# OpenBookReader.net
KiCad netlist of a schematic drawn in EAGLE
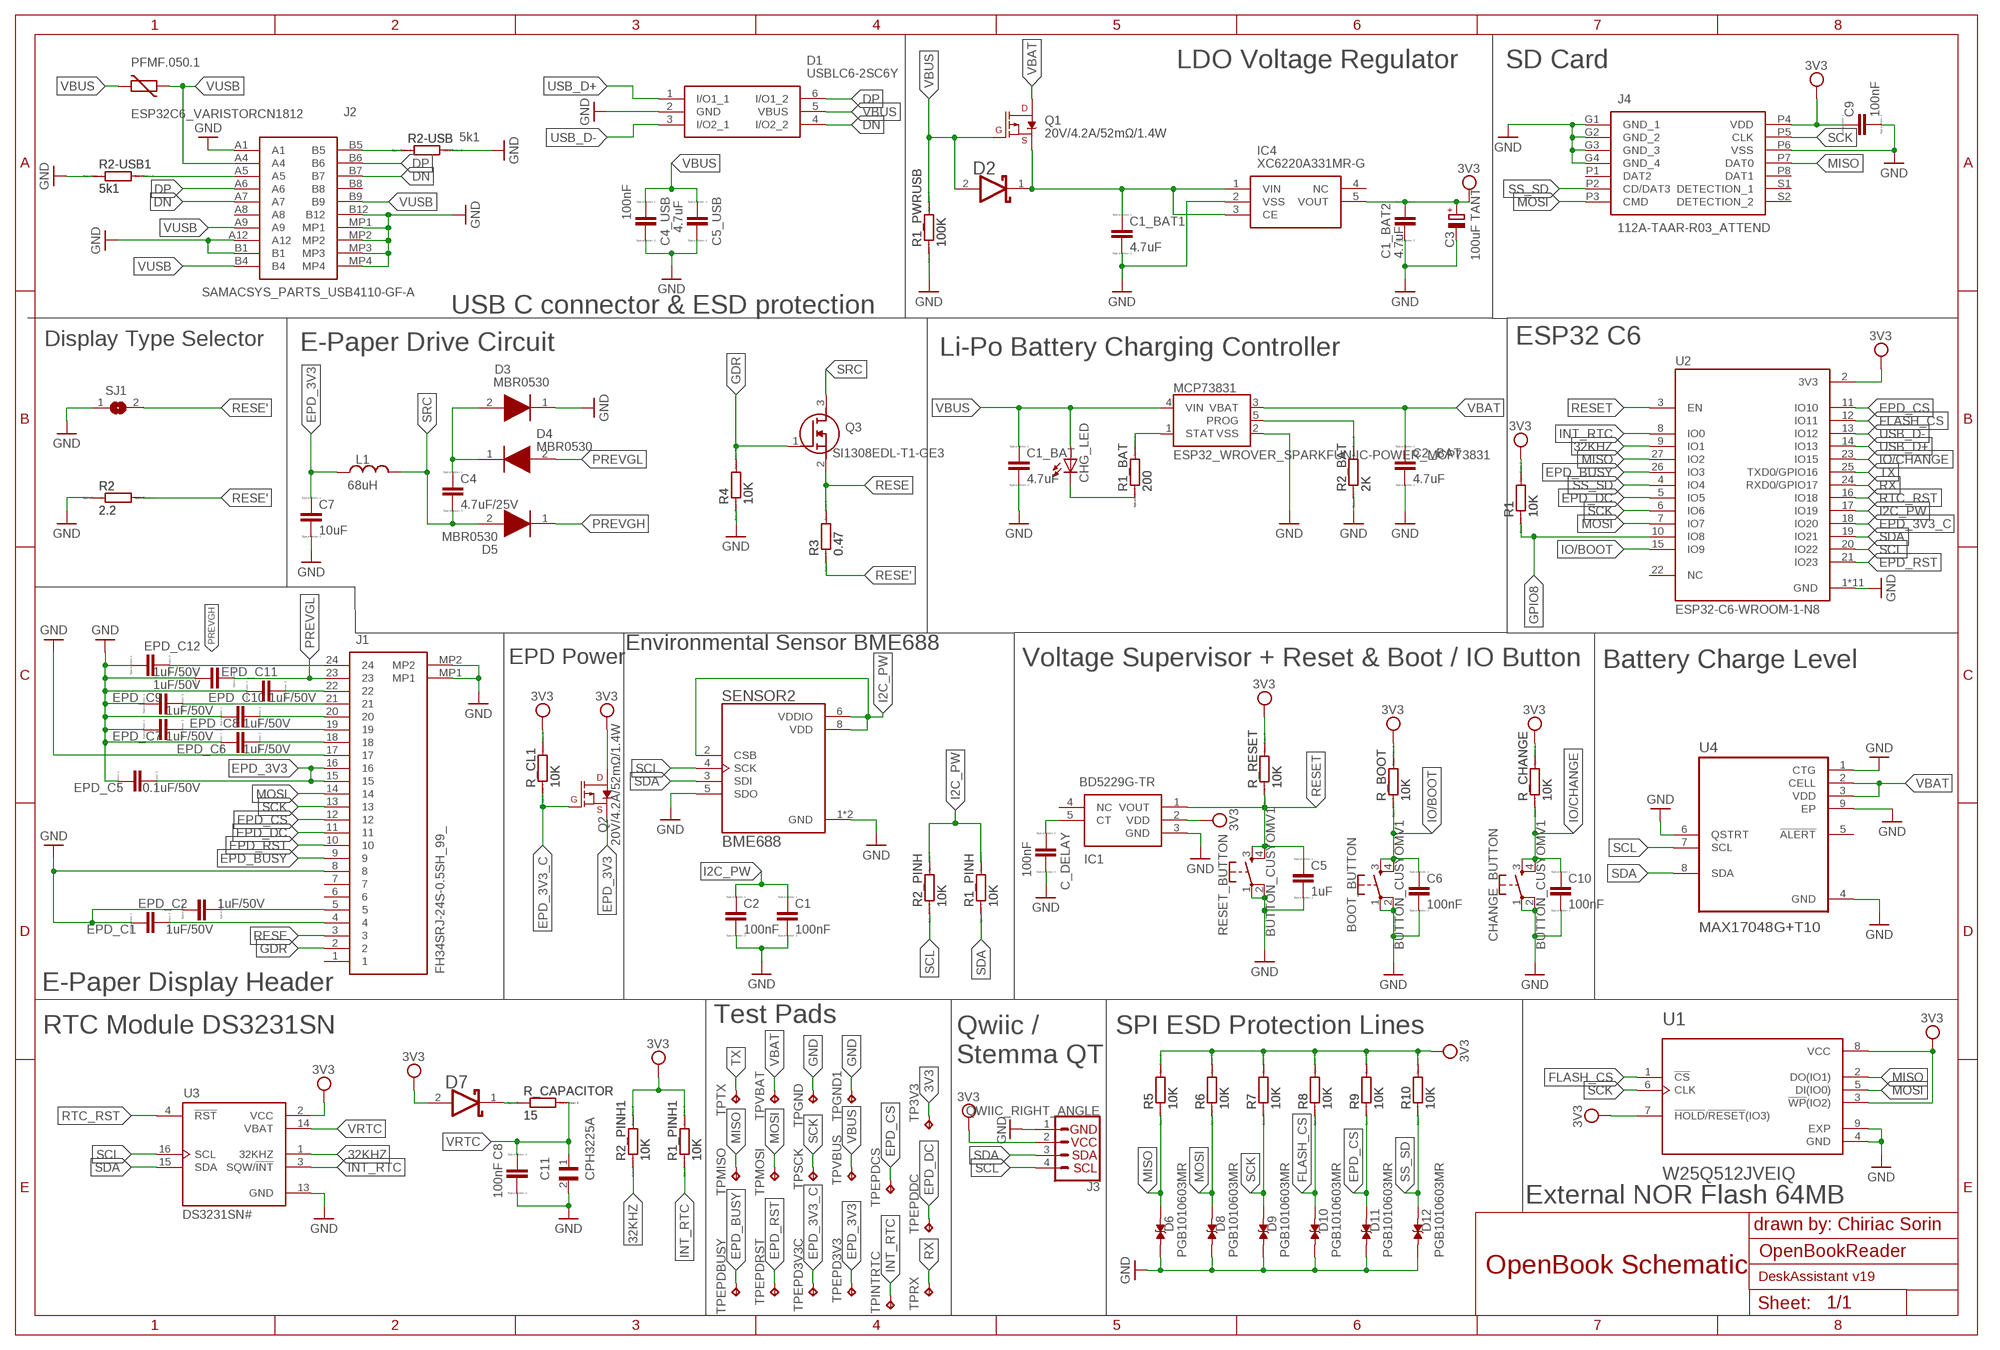
[diagram p0: schematic, sheet 1]

(export (version "E")
  (design (tool "Eeschema 10.0.6"))
  (components
    (comp (ref "BOOT_BUTTON")
      (value "BUTTON_CUSYOMV1")
      (footprint "eagle-import:MYBUTTON")
      (libsource (lib "eagle-import") (part "BUTTON_CUSYOMV1"))
    )
    (comp (ref "C1")
      (value "100nF")
      (footprint "eagle-import:EAGLE-LTSPICE_C0402")
      (libsource (lib "eagle-import") (part "EAGLE-LTSPICE_CC0402"))
    )
    (comp (ref "C1_BAT")
      (value "4.7uF")
      (footprint "eagle-import:EAGLE-LTSPICE_C0402")
      (libsource (lib "eagle-import") (part "EAGLE-LTSPICE_CC0402"))
    )
    (comp (ref "C1_BAT1")
      (value "4.7uF")
      (footprint "eagle-import:EAGLE-LTSPICE_C0402")
      (libsource (lib "eagle-import") (part "EAGLE-LTSPICE_CC0402"))
    )
    (comp (ref "C1_BAT2")
      (value "4.7uF")
      (footprint "eagle-import:EAGLE-LTSPICE_C0402")
      (libsource (lib "eagle-import") (part "EAGLE-LTSPICE_CC0402"))
    )
    (comp (ref "C2")
      (value "100nF")
      (footprint "eagle-import:EAGLE-LTSPICE_C0402")
      (libsource (lib "eagle-import") (part "EAGLE-LTSPICE_CC0402"))
    )
    (comp (ref "C2_BAT")
      (value "4.7uF")
      (footprint "eagle-import:EAGLE-LTSPICE_C0402")
      (libsource (lib "eagle-import") (part "EAGLE-LTSPICE_CC0402"))
    )
    (comp (ref "C3")
      (value "100uF TANT")
      (footprint "eagle-import:RCL_CT3528")
      (libsource (lib "eagle-import") (part "RCL_CPOL-EUCT3528"))
    )
    (comp (ref "C4")
      (value "4.7uF/25V")
      (footprint "eagle-import:EAGLE-LTSPICE_C0402")
      (libsource (lib "eagle-import") (part "EAGLE-LTSPICE_CC0402"))
    )
    (comp (ref "C4_USB")
      (value "100nF")
      (footprint "eagle-import:EAGLE-LTSPICE_C0402")
      (libsource (lib "eagle-import") (part "EAGLE-LTSPICE_CC0402"))
    )
    (comp (ref "C5")
      (value "1uF")
      (footprint "eagle-import:EAGLE-LTSPICE_C0402")
      (libsource (lib "eagle-import") (part "EAGLE-LTSPICE_CC0402"))
    )
    (comp (ref "C5_USB")
      (value "4.7uF")
      (footprint "eagle-import:EAGLE-LTSPICE_C0402")
      (libsource (lib "eagle-import") (part "EAGLE-LTSPICE_CC0402"))
    )
    (comp (ref "C6")
      (value "100nF")
      (footprint "eagle-import:EAGLE-LTSPICE_C0402")
      (libsource (lib "eagle-import") (part "EAGLE-LTSPICE_CC0402"))
    )
    (comp (ref "C7")
      (value "10uF")
      (footprint "eagle-import:EAGLE-LTSPICE_C0402")
      (libsource (lib "eagle-import") (part "EAGLE-LTSPICE_CC0402"))
    )
    (comp (ref "C8")
      (value "100nF")
      (footprint "eagle-import:EAGLE-LTSPICE_C0402")
      (libsource (lib "eagle-import") (part "EAGLE-LTSPICE_CC0402"))
    )
    (comp (ref "C9")
      (value "100nF")
      (footprint "eagle-import:EAGLE-LTSPICE_C0402")
      (libsource (lib "eagle-import") (part "EAGLE-LTSPICE_CC0402"))
    )
    (comp (ref "C10")
      (value "100nF")
      (footprint "eagle-import:EAGLE-LTSPICE_C0402")
      (libsource (lib "eagle-import") (part "EAGLE-LTSPICE_CC0402"))
    )
    (comp (ref "C11")
      (value "CPH3225A")
      (footprint "eagle-import:CAPCP3225X100N")
      (fields (field (name "MF") "Seiko Instruments"))
      (libsource (lib "eagle-import") (part "CPH3225A"))
    )
    (comp (ref "CHANGE_BUTTON")
      (value "BUTTON_CUSYOMV1")
      (footprint "eagle-import:MYBUTTON")
      (libsource (lib "eagle-import") (part "BUTTON_CUSYOMV1"))
    )
    (comp (ref "CHG_LED")
      (value "ADAFRUIT_LEDCHIP-LED0603")
      (footprint "eagle-import:ADAFRUIT_CHIP-LED0603")
      (libsource (lib "eagle-import") (part "ADAFRUIT_LEDCHIP-LED0603"))
    )
    (comp (ref "C_DELAY")
      (value "100nF")
      (footprint "eagle-import:EAGLE-LTSPICE_C0402")
      (libsource (lib "eagle-import") (part "EAGLE-LTSPICE_CC0402"))
    )
    (comp (ref "D1")
      (value "USBLC6-2SC6Y")
      (footprint "eagle-import:SOT95P280X145-6N")
      (fields (field (name "MF") "STMicroelectronics"))
      (libsource (lib "eagle-import") (part "USBLC6-2SC6Y"))
    )
    (comp (ref "D2")
      (value "ESP32_WROVER_AVX---SD0805S020S1R0_AVX_SD0805S020S1R0_0_0AVX_SD0805S020S1R0_0_0")
      (footprint "eagle-import:ESP32_WROVER_AVX---SD0805S020S1R0_AVX_SD0805S020S1R0_0")
      (fields
        (field (name "DIGIKEY_PART_NUMBER") "478-7800-1-ND")
        (field (name "MF") "AVX")
        (field (name "MOUSER_PART_NUMBER") "581-SD0805S020S1R0")
      )
      (libsource (lib "eagle-import") (part "ESP32_WROVER_AVX---SD0805S020S1R0_AVX_SD0805S020S1R0_0_0AVX_SD0805S020S1R0_0_0"))
    )
    (comp (ref "D3")
      (value "MBR0530")
      (footprint "eagle-import:SOD3716X135N")
      (fields (field (name "MF") "ON Semiconductor"))
      (libsource (lib "eagle-import") (part "MBR0530"))
    )
    (comp (ref "D4")
      (value "MBR0530")
      (footprint "eagle-import:SOD3716X135N")
      (fields (field (name "MF") "ON Semiconductor"))
      (libsource (lib "eagle-import") (part "MBR0530"))
    )
    (comp (ref "D5")
      (value "MBR0530")
      (footprint "eagle-import:SOD3716X135N")
      (fields (field (name "MF") "ON Semiconductor"))
      (libsource (lib "eagle-import") (part "MBR0530"))
    )
    (comp (ref "D6")
      (value "PGB1010603MR")
      (footprint "eagle-import:DIOC1608X36N")
      (fields (field (name "MF") "Littelfuse Inc."))
      (libsource (lib "eagle-import") (part "PGB1010603MR"))
    )
    (comp (ref "D7")
      (value "ESP32_WROVER_AVX---SD0805S020S1R0_AVX_SD0805S020S1R0_0_0AVX_SD0805S020S1R0_0_0")
      (footprint "eagle-import:ESP32_WROVER_AVX---SD0805S020S1R0_AVX_SD0805S020S1R0_0")
      (fields
        (field (name "DIGIKEY_PART_NUMBER") "478-7800-1-ND")
        (field (name "MF") "AVX")
        (field (name "MOUSER_PART_NUMBER") "581-SD0805S020S1R0")
      )
      (libsource (lib "eagle-import") (part "ESP32_WROVER_AVX---SD0805S020S1R0_AVX_SD0805S020S1R0_0_0AVX_SD0805S020S1R0_0_0"))
    )
    (comp (ref "D8")
      (value "PGB1010603MR")
      (footprint "eagle-import:DIOC1608X36N")
      (fields (field (name "MF") "Littelfuse Inc."))
      (libsource (lib "eagle-import") (part "PGB1010603MR"))
    )
    (comp (ref "D9")
      (value "PGB1010603MR")
      (footprint "eagle-import:DIOC1608X36N")
      (fields (field (name "MF") "Littelfuse Inc."))
      (libsource (lib "eagle-import") (part "PGB1010603MR"))
    )
    (comp (ref "D10")
      (value "PGB1010603MR")
      (footprint "eagle-import:DIOC1608X36N")
      (fields (field (name "MF") "Littelfuse Inc."))
      (libsource (lib "eagle-import") (part "PGB1010603MR"))
    )
    (comp (ref "D11")
      (value "PGB1010603MR")
      (footprint "eagle-import:DIOC1608X36N")
      (fields (field (name "MF") "Littelfuse Inc."))
      (libsource (lib "eagle-import") (part "PGB1010603MR"))
    )
    (comp (ref "D12")
      (value "PGB1010603MR")
      (footprint "eagle-import:DIOC1608X36N")
      (fields (field (name "MF") "Littelfuse Inc."))
      (libsource (lib "eagle-import") (part "PGB1010603MR"))
    )
    (comp (ref "EPD_C1")
      (value "1uF/50V")
      (footprint "eagle-import:EAGLE-LTSPICE_C0402")
      (libsource (lib "eagle-import") (part "EAGLE-LTSPICE_CC0402"))
    )
    (comp (ref "EPD_C2")
      (value "1uF/50V")
      (footprint "eagle-import:EAGLE-LTSPICE_C0402")
      (libsource (lib "eagle-import") (part "EAGLE-LTSPICE_CC0402"))
    )
    (comp (ref "EPD_C5")
      (value "0.1uF/50V")
      (footprint "eagle-import:EAGLE-LTSPICE_C0402")
      (libsource (lib "eagle-import") (part "EAGLE-LTSPICE_CC0402"))
    )
    (comp (ref "EPD_C6")
      (value "1uF/50V")
      (footprint "eagle-import:EAGLE-LTSPICE_C0402")
      (libsource (lib "eagle-import") (part "EAGLE-LTSPICE_CC0402"))
    )
    (comp (ref "EPD_C7")
      (value "1uF/50V")
      (footprint "eagle-import:EAGLE-LTSPICE_C0402")
      (libsource (lib "eagle-import") (part "EAGLE-LTSPICE_CC0402"))
    )
    (comp (ref "EPD_C8")
      (value "1uF/50V")
      (footprint "eagle-import:EAGLE-LTSPICE_C0402")
      (libsource (lib "eagle-import") (part "EAGLE-LTSPICE_CC0402"))
    )
    (comp (ref "EPD_C9")
      (value "1uF/50V")
      (footprint "eagle-import:EAGLE-LTSPICE_C0402")
      (libsource (lib "eagle-import") (part "EAGLE-LTSPICE_CC0402"))
    )
    (comp (ref "EPD_C10")
      (value "1uF/50V")
      (footprint "eagle-import:EAGLE-LTSPICE_C0402")
      (libsource (lib "eagle-import") (part "EAGLE-LTSPICE_CC0402"))
    )
    (comp (ref "EPD_C11")
      (value "1uF/50V")
      (footprint "eagle-import:EAGLE-LTSPICE_C0402")
      (libsource (lib "eagle-import") (part "EAGLE-LTSPICE_CC0402"))
    )
    (comp (ref "EPD_C12")
      (value "1uF/50V")
      (footprint "eagle-import:EAGLE-LTSPICE_C0402")
      (libsource (lib "eagle-import") (part "EAGLE-LTSPICE_CC0402"))
    )
    (comp (ref "IC1")
      (value "BD5229G-TR")
      (footprint "eagle-import:SOT95P280X125-5N")
      (fields (field (name "MOUSER_PART_NUMBER") "755-BD5229G-TR"))
      (libsource (lib "eagle-import") (part "BD5229G-TR"))
    )
    (comp (ref "IC4")
      (value "XC6220A331MR-G")
      (footprint "eagle-import:SOT95P280X120-5N")
      (fields (field (name "MOUSER_PART_NUMBER") "865-XC6220A331MR-G"))
      (libsource (lib "eagle-import") (part "XC6220A331MR-G"))
    )
    (comp (ref "J1")
      (value "FH34SRJ-24S-0.5SH_99_")
      (footprint "eagle-import:FH34SRJ24S05SH99")
      (fields
        (field (name "MANUFACTURER_PART_NUMBER") "FH34SRJ-24S-0.5SH(99)")
        (field (name "MOUSER_PART_NUMBER") "798-FH34SRJ24S05SH99")
      )
      (libsource (lib "eagle-import") (part "FH34SRJ-24S-0.5SH_99_"))
    )
    (comp (ref "J2")
      (value "SAMACSYS_PARTS_USB4110-GF-A")
      (footprint "eagle-import:SAMACSYS_PARTS_USB4110GFA")
      (fields
        (field (name "MANUFACTURER_PART_NUMBER") "USB4110-GF-A")
        (field (name "MOUSER_PART_NUMBER") "640-USB4110-GF-A")
      )
      (libsource (lib "eagle-import") (part "SAMACSYS_PARTS_USB4110-GF-A"))
    )
    (comp (ref "J3")
      (value "QWIIC_RIGHT_ANGLE")
      (footprint "eagle-import:JST04_1MM_RA")
      (libsource (lib "eagle-import") (part "QWIIC_CONNECTORJS-1MM"))
    )
    (comp (ref "J4")
      (value "112A-TAAR-R03_ATTEND")
      (footprint "eagle-import:112ATAARR03ATTEND")
      (fields (field (name "MANUFACTURER_PART_NUMBER") "112A-TAAR-R03 ATTEND"))
      (libsource (lib "eagle-import") (part "112A-TAAR-R03_ATTEND"))
    )
    (comp (ref "L1")
      (value "68uH")
      (footprint "eagle-import:INDC1006X60N")
      (libsource (lib "eagle-import") (part "INDUCTORCHIP-0402(1006-METRIC)_"))
    )
    (comp (ref "MCP73831")
      (value "ESP32_WROVER_SPARKFUN-IC-POWER_MCP73831")
      (footprint "eagle-import:ESP32_WROVER_SPARKFUN-IC-POWER_SOT23-5")
      (libsource (lib "eagle-import") (part "ESP32_WROVER_SPARKFUN-IC-POWER_MCP73831"))
    )
    (comp (ref "PFMF.050.1")
      (value "ESP32C6_VARISTORCN1812")
      (footprint "eagle-import:ESP32C6_VARISTOR_CT_CN1812")
      (libsource (lib "eagle-import") (part "ESP32C6_VARISTORCN1812"))
    )
    (comp (ref "Q1")
      (value "20V/4.2A/52mΩ/1.4W")
      (footprint "eagle-import:ESP32_WROVER_SPARKFUN-DISCRETESEMI_SOT23-3")
      (libsource (lib "eagle-import") (part "ESP32_WROVER_SPARKFUN-DISCRETESEMI_MOSFET_PCH-DMG2305UX-7"))
    )
    (comp (ref "Q2")
      (value "20V/4.2A/52mΩ/1.4W")
      (footprint "eagle-import:ESP32_WROVER_SPARKFUN-DISCRETESEMI_SOT23-3")
      (libsource (lib "eagle-import") (part "ESP32_WROVER_SPARKFUN-DISCRETESEMI_MOSFET_PCH-DMG2305UX-7"))
    )
    (comp (ref "Q3")
      (value "SI1308EDL-T1-GE3")
      (footprint "eagle-import:SOT65P210X110-3N")
      (fields (field (name "MF") "Vishay Siliconix"))
      (libsource (lib "eagle-import") (part "SI1308EDL-T1-GE3"))
    )
    (comp (ref "R1")
      (value "10K")
      (footprint "eagle-import:ESP32_WROVER_EAGLE-LTSPICE_R0402")
      (libsource (lib "eagle-import") (part "ESP32_WROVER_EAGLE-LTSPICE_RR0402"))
    )
    (comp (ref "R1_BAT")
      (value "200")
      (footprint "eagle-import:ESP32_WROVER_EAGLE-LTSPICE_R0402")
      (libsource (lib "eagle-import") (part "ESP32_WROVER_EAGLE-LTSPICE_RR0402"))
    )
    (comp (ref "R1_PINH")
      (value "10K")
      (footprint "eagle-import:ESP32_WROVER_EAGLE-LTSPICE_R0402")
      (libsource (lib "eagle-import") (part "ESP32_WROVER_EAGLE-LTSPICE_RR0402"))
    )
    (comp (ref "R1_PINH1")
      (value "10K")
      (footprint "eagle-import:ESP32_WROVER_EAGLE-LTSPICE_R0402")
      (libsource (lib "eagle-import") (part "ESP32_WROVER_EAGLE-LTSPICE_RR0402"))
    )
    (comp (ref "R1_PWRUSB")
      (value "100K")
      (footprint "eagle-import:ESP32_WROVER_EAGLE-LTSPICE_R0402")
      (libsource (lib "eagle-import") (part "ESP32_WROVER_EAGLE-LTSPICE_RR0402"))
    )
    (comp (ref "R2")
      (value "2.2")
      (footprint "eagle-import:ESP32_WROVER_EAGLE-LTSPICE_R0402")
      (libsource (lib "eagle-import") (part "ESP32_WROVER_EAGLE-LTSPICE_RR0402"))
    )
    (comp (ref "R2-USB")
      (value "5k1")
      (footprint "eagle-import:ESP32_WROVER_EAGLE-LTSPICE_R0402")
      (libsource (lib "eagle-import") (part "ESP32_WROVER_EAGLE-LTSPICE_RR0402"))
    )
    (comp (ref "R2-USB1")
      (value "5k1")
      (footprint "eagle-import:ESP32_WROVER_EAGLE-LTSPICE_R0402")
      (libsource (lib "eagle-import") (part "ESP32_WROVER_EAGLE-LTSPICE_RR0402"))
    )
    (comp (ref "R2_BAT")
      (value "2K")
      (footprint "eagle-import:ESP32_WROVER_EAGLE-LTSPICE_R0402")
      (libsource (lib "eagle-import") (part "ESP32_WROVER_EAGLE-LTSPICE_RR0402"))
    )
    (comp (ref "R2_PINH")
      (value "10K")
      (footprint "eagle-import:ESP32_WROVER_EAGLE-LTSPICE_R0402")
      (libsource (lib "eagle-import") (part "ESP32_WROVER_EAGLE-LTSPICE_RR0402"))
    )
    (comp (ref "R2_PINH1")
      (value "10K")
      (footprint "eagle-import:ESP32_WROVER_EAGLE-LTSPICE_R0402")
      (libsource (lib "eagle-import") (part "ESP32_WROVER_EAGLE-LTSPICE_RR0402"))
    )
    (comp (ref "R3")
      (value "0.47")
      (footprint "eagle-import:ESP32_WROVER_EAGLE-LTSPICE_R0402")
      (libsource (lib "eagle-import") (part "ESP32_WROVER_EAGLE-LTSPICE_RR0402"))
    )
    (comp (ref "R4")
      (value "10K")
      (footprint "eagle-import:ESP32_WROVER_EAGLE-LTSPICE_R0402")
      (libsource (lib "eagle-import") (part "ESP32_WROVER_EAGLE-LTSPICE_RR0402"))
    )
    (comp (ref "R5")
      (value "10K")
      (footprint "eagle-import:ESP32_WROVER_EAGLE-LTSPICE_R0402")
      (libsource (lib "eagle-import") (part "ESP32_WROVER_EAGLE-LTSPICE_RR0402"))
    )
    (comp (ref "R6")
      (value "10K")
      (footprint "eagle-import:ESP32_WROVER_EAGLE-LTSPICE_R0402")
      (libsource (lib "eagle-import") (part "ESP32_WROVER_EAGLE-LTSPICE_RR0402"))
    )
    (comp (ref "R7")
      (value "10K")
      (footprint "eagle-import:ESP32_WROVER_EAGLE-LTSPICE_R0402")
      (libsource (lib "eagle-import") (part "ESP32_WROVER_EAGLE-LTSPICE_RR0402"))
    )
    (comp (ref "R8")
      (value "10K")
      (footprint "eagle-import:ESP32_WROVER_EAGLE-LTSPICE_R0402")
      (libsource (lib "eagle-import") (part "ESP32_WROVER_EAGLE-LTSPICE_RR0402"))
    )
    (comp (ref "R9")
      (value "10K")
      (footprint "eagle-import:ESP32_WROVER_EAGLE-LTSPICE_R0402")
      (libsource (lib "eagle-import") (part "ESP32_WROVER_EAGLE-LTSPICE_RR0402"))
    )
    (comp (ref "R10")
      (value "10K")
      (footprint "eagle-import:ESP32_WROVER_EAGLE-LTSPICE_R0402")
      (libsource (lib "eagle-import") (part "ESP32_WROVER_EAGLE-LTSPICE_RR0402"))
    )
    (comp (ref "RESET_BUTTON")
      (value "BUTTON_CUSYOMV1")
      (footprint "eagle-import:MYBUTTON")
      (libsource (lib "eagle-import") (part "BUTTON_CUSYOMV1"))
    )
    (comp (ref "R_BOOT")
      (value "10K")
      (footprint "eagle-import:ESP32_WROVER_EAGLE-LTSPICE_R0402")
      (libsource (lib "eagle-import") (part "ESP32_WROVER_EAGLE-LTSPICE_RR0402"))
    )
    (comp (ref "R_CAPACITOR")
      (value "15")
      (footprint "eagle-import:ESP32_WROVER_EAGLE-LTSPICE_R0402")
      (libsource (lib "eagle-import") (part "ESP32_WROVER_EAGLE-LTSPICE_RR0402"))
    )
    (comp (ref "R_CHANGE")
      (value "10K")
      (footprint "eagle-import:ESP32_WROVER_EAGLE-LTSPICE_R0402")
      (libsource (lib "eagle-import") (part "ESP32_WROVER_EAGLE-LTSPICE_RR0402"))
    )
    (comp (ref "R_CL1")
      (value "10K")
      (footprint "eagle-import:ESP32_WROVER_EAGLE-LTSPICE_R0402")
      (libsource (lib "eagle-import") (part "ESP32_WROVER_EAGLE-LTSPICE_RR0402"))
    )
    (comp (ref "R_RESET")
      (value "10K")
      (footprint "eagle-import:ESP32_WROVER_EAGLE-LTSPICE_R0402")
      (libsource (lib "eagle-import") (part "ESP32_WROVER_EAGLE-LTSPICE_RR0402"))
    )
    (comp (ref "SENSOR2")
      (value "BME688")
      (footprint "eagle-import:ESP32_WROVER_BME680_PSON80P300X300X100-8N")
      (fields (field (name "MF") "Bosch Sensortec") (field (name "MP") "BME680"))
      (libsource (lib "eagle-import") (part "ESP32_WROVER_BME680_BME680"))
    )
    (comp (ref "SJ1") (value "SJ") (footprint "eagle-import:SJ") (libsource (lib "eagle-import") (part "SJ")))
    (comp (ref "TP3V3")
      (value "TPTP20R")
      (footprint "eagle-import:TP20R")
      (libsource (lib "eagle-import") (part "TPTP20R"))
    )
    (comp (ref "TPEPD3V3")
      (value "TPTP20R")
      (footprint "eagle-import:TP20R")
      (libsource (lib "eagle-import") (part "TPTP20R"))
    )
    (comp (ref "TPEPD3V3C")
      (value "TPTP20R")
      (footprint "eagle-import:TP20R")
      (libsource (lib "eagle-import") (part "TPTP20R"))
    )
    (comp (ref "TPEPDBUSY")
      (value "TPTP20R")
      (footprint "eagle-import:TP20R")
      (libsource (lib "eagle-import") (part "TPTP20R"))
    )
    (comp (ref "TPEPDCS")
      (value "TPTP20R")
      (footprint "eagle-import:TP20R")
      (libsource (lib "eagle-import") (part "TPTP20R"))
    )
    (comp (ref "TPEPDDC")
      (value "TPTP20R")
      (footprint "eagle-import:TP20R")
      (libsource (lib "eagle-import") (part "TPTP20R"))
    )
    (comp (ref "TPEPDRST")
      (value "TPTP20R")
      (footprint "eagle-import:TP20R")
      (libsource (lib "eagle-import") (part "TPTP20R"))
    )
    (comp (ref "TPGND")
      (value "TPTP20R")
      (footprint "eagle-import:TP20R")
      (libsource (lib "eagle-import") (part "TPTP20R"))
    )
    (comp (ref "TPGND1")
      (value "TPTP20R")
      (footprint "eagle-import:TP20R")
      (libsource (lib "eagle-import") (part "TPTP20R"))
    )
    (comp (ref "TPINTRTC")
      (value "TPTP20R")
      (footprint "eagle-import:TP20R")
      (libsource (lib "eagle-import") (part "TPTP20R"))
    )
    (comp (ref "TPMISO")
      (value "TPTP20R")
      (footprint "eagle-import:TP20R")
      (libsource (lib "eagle-import") (part "TPTP20R"))
    )
    (comp (ref "TPMOSI")
      (value "TPTP20R")
      (footprint "eagle-import:TP20R")
      (libsource (lib "eagle-import") (part "TPTP20R"))
    )
    (comp (ref "TPRX")
      (value "TPTP20R")
      (footprint "eagle-import:TP20R")
      (libsource (lib "eagle-import") (part "TPTP20R"))
    )
    (comp (ref "TPSCK")
      (value "TPTP20R")
      (footprint "eagle-import:TP20R")
      (libsource (lib "eagle-import") (part "TPTP20R"))
    )
    (comp (ref "TPTX")
      (value "TPTP20R")
      (footprint "eagle-import:TP20R")
      (libsource (lib "eagle-import") (part "TPTP20R"))
    )
    (comp (ref "TPVBAT")
      (value "TPTP20R")
      (footprint "eagle-import:TP20R")
      (libsource (lib "eagle-import") (part "TPTP20R"))
    )
    (comp (ref "TPVBUS")
      (value "TPTP20R")
      (footprint "eagle-import:TP20R")
      (libsource (lib "eagle-import") (part "TPTP20R"))
    )
    (comp (ref "U1")
      (value "W25Q512JVEIQ")
      (footprint "eagle-import:SON127P600X800X80-9N")
      (fields (field (name "MF") "Winbond Electronics"))
      (libsource (lib "eagle-import") (part "W25Q512JVEIQ"))
    )
    (comp (ref "U2")
      (value "ESP32-C6-WROOM-1-N8")
      (footprint "eagle-import:XCVR_ESP32-C6-WROOM-1-N8")
      (fields (field (name "MF") "Espressif Systems"))
      (libsource (lib "eagle-import") (part "ESP32-C6-WROOM-1-N8"))
    )
    (comp (ref "U3")
      (value "DS3231SN#")
      (footprint "eagle-import:SOIC127P1032X265-16N")
      (fields (field (name "MF") "Analog Devices"))
      (libsource (lib "eagle-import") (part "DS3231SN#"))
    )
    (comp (ref "U4")
      (value "MAX17048G+T10")
      (footprint "eagle-import:SON50P200X200X80-9N")
      (fields (field (name "MF") "Analog Devices"))
      (libsource (lib "eagle-import") (part "MAX17048G+T10"))
    )
  )
  (nets
    (net (code "1") (name "3V3") (class "Default")
      (node (ref "C1_BAT2") (pin "1") (pinfunction "1_1") (pintype "passive"))
      (node (ref "C3") (pin "+") (pinfunction "+_+") (pintype "passive"))
      (node (ref "C9") (pin "1") (pinfunction "1_1") (pintype "passive"))
      (node (ref "D7") (pin "2") (pinfunction "ANODE_2") (pintype "bidirectional"))
      (node (ref "IC1") (pin "2") (pinfunction "VDD_2") (pintype "bidirectional"))
      (node (ref "IC4") (pin "5") (pinfunction "VOUT_5") (pintype "bidirectional"))
      (node (ref "J3") (pin "2") (pinfunction "2_2") (pintype "power_in"))
      (node (ref "J4") (pin "P4") (pinfunction "VDD_P4") (pintype "bidirectional"))
      (node (ref "Q2") (pin "3") (pinfunction "D_3") (pintype "bidirectional"))
      (node (ref "R1") (pin "2") (pinfunction "2_2") (pintype "passive"))
      (node (ref "R10") (pin "2") (pinfunction "2_2") (pintype "passive"))
      (node (ref "R1_PINH1") (pin "2") (pinfunction "2_2") (pintype "passive"))
      (node (ref "R2_PINH1") (pin "2") (pinfunction "2_2") (pintype "passive"))
      (node (ref "R5") (pin "2") (pinfunction "2_2") (pintype "passive"))
      (node (ref "R6") (pin "2") (pinfunction "2_2") (pintype "passive"))
      (node (ref "R7") (pin "2") (pinfunction "2_2") (pintype "passive"))
      (node (ref "R8") (pin "2") (pinfunction "2_2") (pintype "passive"))
      (node (ref "R9") (pin "2") (pinfunction "2_2") (pintype "passive"))
      (node (ref "R_BOOT") (pin "2") (pinfunction "2_2") (pintype "passive"))
      (node (ref "R_CHANGE") (pin "2") (pinfunction "2_2") (pintype "passive"))
      (node (ref "R_CL1") (pin "2") (pinfunction "2_2") (pintype "passive"))
      (node (ref "R_RESET") (pin "2") (pinfunction "2_2") (pintype "passive"))
      (node (ref "TP3V3") (pin "TP") (pinfunction "TP_TP") (pintype "input"))
      (node (ref "U1") (pin "3") (pinfunction "~{WP}(IO2)_3") (pintype "bidirectional"))
      (node (ref "U1") (pin "7") (pinfunction "~{HOLD}/~{RESET}(IO3)_7") (pintype "bidirectional"))
      (node (ref "U1") (pin "8") (pinfunction "VCC_8") (pintype "power_in"))
      (node (ref "U2") (pin "2") (pinfunction "3V3_2") (pintype "power_in"))
      (node (ref "U3") (pin "2") (pinfunction "VCC_2") (pintype "power_in"))
    )
    (net (code "2") (name "32KHZ") (class "Default")
      (node (ref "R2_PINH1") (pin "1") (pinfunction "1_1") (pintype "passive"))
      (node (ref "U2") (pin "9") (pinfunction "IO1_9") (pintype "bidirectional"))
      (node (ref "U3") (pin "1") (pinfunction "32KHZ_1") (pintype "output"))
    )
    (net (code "3") (name "DN") (class "Default")
      (node (ref "D1") (pin "4") (pinfunction "I/O2_2_4") (pintype "bidirectional"))
      (node (ref "J2") (pin "A7") (pinfunction "A7_A7") (pintype "bidirectional"))
      (node (ref "J2") (pin "B7") (pinfunction "B7_B7") (pintype "bidirectional"))
    )
    (net (code "4") (name "DP") (class "Default")
      (node (ref "D1") (pin "6") (pinfunction "I/O1_2_6") (pintype "bidirectional"))
      (node (ref "J2") (pin "A6") (pinfunction "A6_A6") (pintype "bidirectional"))
      (node (ref "J2") (pin "B6") (pinfunction "B6_B6") (pintype "bidirectional"))
    )
    (net (code "5") (name "EPD_3V3") (class "Default")
      (node (ref "C7") (pin "1") (pinfunction "1_1") (pintype "passive"))
      (node (ref "EPD_C5") (pin "2") (pinfunction "2_2") (pintype "passive"))
      (node (ref "J1") (pin "15") (pinfunction "15_15") (pintype "bidirectional"))
      (node (ref "J1") (pin "16") (pinfunction "16_16") (pintype "bidirectional"))
      (node (ref "L1") (pin "1") (pinfunction "1_1") (pintype "passive"))
      (node (ref "Q2") (pin "2") (pinfunction "S_2") (pintype "bidirectional"))
      (node (ref "TPEPD3V3") (pin "TP") (pinfunction "TP_TP") (pintype "input"))
    )
    (net (code "6") (name "EPD_3V3_C") (class "Default")
      (node (ref "Q2") (pin "1") (pinfunction "G_1") (pintype "bidirectional"))
      (node (ref "R_CL1") (pin "1") (pinfunction "1_1") (pintype "passive"))
      (node (ref "TPEPD3V3C") (pin "TP") (pinfunction "TP_TP") (pintype "input"))
      (node (ref "U2") (pin "18") (pinfunction "IO20_18") (pintype "bidirectional"))
    )
    (net (code "7") (name "EPD_BUSY") (class "Default")
      (node (ref "J1") (pin "9") (pinfunction "9_9") (pintype "bidirectional"))
      (node (ref "TPEPDBUSY") (pin "TP") (pinfunction "TP_TP") (pintype "input"))
      (node (ref "U2") (pin "26") (pinfunction "IO3_26") (pintype "bidirectional"))
    )
    (net (code "8") (name "EPD_CS") (class "Default")
      (node (ref "D11") (pin "2") (pinfunction "2_2") (pintype "passive"))
      (node (ref "J1") (pin "12") (pinfunction "12_12") (pintype "bidirectional"))
      (node (ref "R9") (pin "1") (pinfunction "1_1") (pintype "passive"))
      (node (ref "TPEPDCS") (pin "TP") (pinfunction "TP_TP") (pintype "input"))
      (node (ref "U2") (pin "11") (pinfunction "IO10_11") (pintype "bidirectional"))
    )
    (net (code "9") (name "EPD_DC") (class "Default")
      (node (ref "J1") (pin "11") (pinfunction "11_11") (pintype "bidirectional"))
      (node (ref "TPEPDDC") (pin "TP") (pinfunction "TP_TP") (pintype "input"))
      (node (ref "U2") (pin "5") (pinfunction "IO5_5") (pintype "bidirectional"))
    )
    (net (code "10") (name "EPD_RST") (class "Default")
      (node (ref "J1") (pin "10") (pinfunction "10_10") (pintype "bidirectional"))
      (node (ref "TPEPDRST") (pin "TP") (pinfunction "TP_TP") (pintype "input"))
      (node (ref "U2") (pin "21") (pinfunction "IO23_21") (pintype "bidirectional"))
    )
    (net (code "11") (name "FLASH_CS") (class "Default")
      (node (ref "D10") (pin "2") (pinfunction "2_2") (pintype "passive"))
      (node (ref "R8") (pin "1") (pinfunction "1_1") (pintype "passive"))
      (node (ref "U1") (pin "1") (pinfunction "~{CS}_1") (pintype "input"))
      (node (ref "U2") (pin "12") (pinfunction "IO11_12") (pintype "bidirectional"))
    )
    (net (code "12") (name "GDR") (class "Default")
      (node (ref "J1") (pin "2") (pinfunction "2_2") (pintype "bidirectional"))
      (node (ref "Q3") (pin "1") (pinfunction "G_1") (pintype "bidirectional"))
      (node (ref "R4") (pin "2") (pinfunction "2_2") (pintype "passive"))
    )
    (net (code "13") (name "GND") (class "Default")
      (node (ref "BOOT_BUTTON") (pin "1") (pinfunction "1_1") (pintype "passive"))
      (node (ref "BOOT_BUTTON") (pin "2") (pinfunction "2_2") (pintype "passive"))
      (node (ref "C1") (pin "2") (pinfunction "2_2") (pintype "passive"))
      (node (ref "C10") (pin "2") (pinfunction "2_2") (pintype "passive"))
      (node (ref "C11") (pin "2") (pinfunction "2_2") (pintype "passive"))
      (node (ref "C1_BAT") (pin "2") (pinfunction "2_2") (pintype "passive"))
      (node (ref "C1_BAT1") (pin "2") (pinfunction "2_2") (pintype "passive"))
      (node (ref "C1_BAT2") (pin "2") (pinfunction "2_2") (pintype "passive"))
      (node (ref "C2") (pin "2") (pinfunction "2_2") (pintype "passive"))
      (node (ref "C2_BAT") (pin "2") (pinfunction "2_2") (pintype "passive"))
      (node (ref "C3") (pin "-") (pinfunction "-_-") (pintype "passive"))
      (node (ref "C4_USB") (pin "2") (pinfunction "2_2") (pintype "passive"))
      (node (ref "C5") (pin "2") (pinfunction "2_2") (pintype "passive"))
      (node (ref "C5_USB") (pin "2") (pinfunction "2_2") (pintype "passive"))
      (node (ref "C6") (pin "2") (pinfunction "2_2") (pintype "passive"))
      (node (ref "C7") (pin "2") (pinfunction "2_2") (pintype "passive"))
      (node (ref "C8") (pin "2") (pinfunction "2_2") (pintype "passive"))
      (node (ref "C9") (pin "2") (pinfunction "2_2") (pintype "passive"))
      (node (ref "CHANGE_BUTTON") (pin "1") (pinfunction "1_1") (pintype "passive"))
      (node (ref "CHANGE_BUTTON") (pin "2") (pinfunction "2_2") (pintype "passive"))
      (node (ref "C_DELAY") (pin "2") (pinfunction "2_2") (pintype "passive"))
      (node (ref "D1") (pin "2") (pinfunction "GND_2") (pintype "bidirectional"))
      (node (ref "D10") (pin "1") (pinfunction "1_1") (pintype "passive"))
      (node (ref "D11") (pin "1") (pinfunction "1_1") (pintype "passive"))
      (node (ref "D12") (pin "1") (pinfunction "1_1") (pintype "passive"))
      (node (ref "D3") (pin "1") (pinfunction "K_1") (pintype "bidirectional"))
      (node (ref "D6") (pin "1") (pinfunction "1_1") (pintype "passive"))
      (node (ref "D8") (pin "1") (pinfunction "1_1") (pintype "passive"))
      (node (ref "D9") (pin "1") (pinfunction "1_1") (pintype "passive"))
      (node (ref "EPD_C1") (pin "1") (pinfunction "1_1") (pintype "passive"))
      (node (ref "EPD_C10") (pin "1") (pinfunction "1_1") (pintype "passive"))
      (node (ref "EPD_C11") (pin "1") (pinfunction "1_1") (pintype "passive"))
      (node (ref "EPD_C12") (pin "1") (pinfunction "1_1") (pintype "passive"))
      (node (ref "EPD_C2") (pin "1") (pinfunction "1_1") (pintype "passive"))
      (node (ref "EPD_C5") (pin "1") (pinfunction "1_1") (pintype "passive"))
      (node (ref "EPD_C6") (pin "1") (pinfunction "1_1") (pintype "passive"))
      (node (ref "EPD_C7") (pin "1") (pinfunction "1_1") (pintype "passive"))
      (node (ref "EPD_C8") (pin "1") (pinfunction "1_1") (pintype "passive"))
      (node (ref "EPD_C9") (pin "1") (pinfunction "1_1") (pintype "passive"))
      (node (ref "IC1") (pin "3") (pinfunction "GND_3") (pintype "bidirectional"))
      (node (ref "IC4") (pin "2") (pinfunction "VSS_2") (pintype "bidirectional"))
      (node (ref "J1") (pin "17") (pinfunction "17_17") (pintype "bidirectional"))
      (node (ref "J1") (pin "8") (pinfunction "8_8") (pintype "bidirectional"))
      (node (ref "J1") (pin "MP1") (pinfunction "MP1_MP1") (pintype "bidirectional"))
      (node (ref "J1") (pin "MP2") (pinfunction "MP2_MP2") (pintype "bidirectional"))
      (node (ref "J2") (pin "A1") (pinfunction "A1_A1") (pintype "bidirectional"))
      (node (ref "J2") (pin "A12") (pinfunction "A12_A12") (pintype "bidirectional"))
      (node (ref "J2") (pin "B1") (pinfunction "B1_B1") (pintype "bidirectional"))
      (node (ref "J2") (pin "B12") (pinfunction "B12_B12") (pintype "bidirectional"))
      (node (ref "J2") (pin "MP1") (pinfunction "MP1_MP1") (pintype "bidirectional"))
      (node (ref "J2") (pin "MP2") (pinfunction "MP2_MP2") (pintype "bidirectional"))
      (node (ref "J2") (pin "MP3") (pinfunction "MP3_MP3") (pintype "bidirectional"))
      (node (ref "J2") (pin "MP4") (pinfunction "MP4_MP4") (pintype "bidirectional"))
      (node (ref "J3") (pin "1") (pinfunction "1_1") (pintype "power_in"))
      (node (ref "J4") (pin "G1") (pinfunction "GND_1_G1") (pintype "bidirectional"))
      (node (ref "J4") (pin "G2") (pinfunction "GND_2_G2") (pintype "bidirectional"))
      (node (ref "J4") (pin "G3") (pinfunction "GND_3_G3") (pintype "bidirectional"))
      (node (ref "J4") (pin "G4") (pinfunction "GND_4_G4") (pintype "bidirectional"))
      (node (ref "J4") (pin "P6") (pinfunction "VSS_P6") (pintype "bidirectional"))
      (node (ref "MCP73831") (pin "2") (pinfunction "VSS_2") (pintype "power_in"))
      (node (ref "R1_PWRUSB") (pin "1") (pinfunction "1_1") (pintype "passive"))
      (node (ref "R2") (pin "1") (pinfunction "1_1") (pintype "passive"))
      (node (ref "R2-USB") (pin "2") (pinfunction "2_2") (pintype "passive"))
      (node (ref "R2-USB1") (pin "1") (pinfunction "1_1") (pintype "passive"))
      (node (ref "R2_BAT") (pin "1") (pinfunction "1_1") (pintype "passive"))
      (node (ref "R4") (pin "1") (pinfunction "1_1") (pintype "passive"))
      (node (ref "RESET_BUTTON") (pin "1") (pinfunction "1_1") (pintype "passive"))
      (node (ref "RESET_BUTTON") (pin "2") (pinfunction "2_2") (pintype "passive"))
      (node (ref "SENSOR2") (pin "1") (pinfunction "GND_1") (pintype "power_in"))
      (node (ref "SENSOR2") (pin "5") (pinfunction "SDO_5") (pintype "bidirectional"))
      (node (ref "SENSOR2") (pin "7") (pinfunction "GND_7") (pintype "power_in"))
      (node (ref "SJ1") (pin "1") (pinfunction "1_1") (pintype "passive"))
      (node (ref "TPGND") (pin "TP") (pinfunction "TP_TP") (pintype "input"))
      (node (ref "TPGND1") (pin "TP") (pinfunction "TP_TP") (pintype "input"))
      (node (ref "U1") (pin "4") (pinfunction "GND_4") (pintype "power_in"))
      (node (ref "U1") (pin "9") (pinfunction "EXP_9") (pintype "passive"))
      (node (ref "U2") (pin "1") (pinfunction "GND_1") (pintype "power_in"))
      (node (ref "U2") (pin "28") (pinfunction "GND_28") (pintype "power_in"))
      (node (ref "U2") (pin "29_1") (pinfunction "GND_29_1") (pintype "power_in"))
      (node (ref "U2") (pin "29_2") (pinfunction "GND_29_2") (pintype "power_in"))
      (node (ref "U2") (pin "29_3") (pinfunction "GND_29_3") (pintype "power_in"))
      (node (ref "U2") (pin "29_4") (pinfunction "GND_29_4") (pintype "power_in"))
      (node (ref "U2") (pin "29_5") (pinfunction "GND_29_5") (pintype "power_in"))
      (node (ref "U2") (pin "29_6") (pinfunction "GND_29_6") (pintype "power_in"))
      (node (ref "U2") (pin "29_7") (pinfunction "GND_29_7") (pintype "power_in"))
      (node (ref "U2") (pin "29_8") (pinfunction "GND_29_8") (pintype "power_in"))
      (node (ref "U2") (pin "29_9") (pinfunction "GND_29_9") (pintype "power_in"))
      (node (ref "U3") (pin "13") (pinfunction "GND_13") (pintype "power_in"))
      (node (ref "U4") (pin "1") (pinfunction "CTG_1") (pintype "power_in"))
      (node (ref "U4") (pin "4") (pinfunction "GND_4") (pintype "power_in"))
      (node (ref "U4") (pin "6") (pinfunction "QSTRT_6") (pintype "input"))
      (node (ref "U4") (pin "9") (pinfunction "EP_9") (pintype "power_in"))
    )
    (net (code "14") (name "GPIO8") (class "Default")
      (node (ref "R1") (pin "1") (pinfunction "1_1") (pintype "passive"))
      (node (ref "U2") (pin "10") (pinfunction "IO8_10") (pintype "bidirectional"))
    )
    (net (code "15") (name "I2C_PW") (class "Default")
      (node (ref "C1") (pin "1") (pinfunction "1_1") (pintype "passive"))
      (node (ref "C2") (pin "1") (pinfunction "1_1") (pintype "passive"))
      (node (ref "R1_PINH") (pin "2") (pinfunction "2_2") (pintype "passive"))
      (node (ref "R2_PINH") (pin "2") (pinfunction "2_2") (pintype "passive"))
      (node (ref "SENSOR2") (pin "2") (pinfunction "CSB_2") (pintype "input"))
      (node (ref "SENSOR2") (pin "6") (pinfunction "VDDIO_6") (pintype "power_in"))
      (node (ref "SENSOR2") (pin "8") (pinfunction "VDD_8") (pintype "power_in"))
      (node (ref "U2") (pin "17") (pinfunction "IO19_17") (pintype "bidirectional"))
    )
    (net (code "16") (name "INT_RTC") (class "Default")
      (node (ref "R1_PINH1") (pin "1") (pinfunction "1_1") (pintype "passive"))
      (node (ref "TPINTRTC") (pin "TP") (pinfunction "TP_TP") (pintype "input"))
      (node (ref "U2") (pin "8") (pinfunction "IO0_8") (pintype "bidirectional"))
      (node (ref "U3") (pin "3") (pinfunction "SQW/~{INT}_3") (pintype "output"))
    )
    (net (code "17") (name "IO{slash}BOOT") (class "Default")
      (node (ref "BOOT_BUTTON") (pin "3") (pinfunction "3_3") (pintype "passive"))
      (node (ref "BOOT_BUTTON") (pin "4") (pinfunction "4_4") (pintype "passive"))
      (node (ref "C6") (pin "1") (pinfunction "1_1") (pintype "passive"))
      (node (ref "R_BOOT") (pin "1") (pinfunction "1_1") (pintype "passive"))
      (node (ref "U2") (pin "15") (pinfunction "IO9_15") (pintype "bidirectional"))
    )
    (net (code "18") (name "IO{slash}CHANGE") (class "Default")
      (node (ref "C10") (pin "1") (pinfunction "1_1") (pintype "passive"))
      (node (ref "CHANGE_BUTTON") (pin "3") (pinfunction "3_3") (pintype "passive"))
      (node (ref "CHANGE_BUTTON") (pin "4") (pinfunction "4_4") (pintype "passive"))
      (node (ref "R_CHANGE") (pin "1") (pinfunction "1_1") (pintype "passive"))
      (node (ref "U2") (pin "23") (pinfunction "IO15_23") (pintype "bidirectional"))
    )
    (net (code "19") (name "MISO") (class "Default")
      (node (ref "D6") (pin "2") (pinfunction "2_2") (pintype "passive"))
      (node (ref "J4") (pin "P7") (pinfunction "DAT0_P7") (pintype "bidirectional"))
      (node (ref "R5") (pin "1") (pinfunction "1_1") (pintype "passive"))
      (node (ref "TPMISO") (pin "TP") (pinfunction "TP_TP") (pintype "input"))
      (node (ref "U1") (pin "2") (pinfunction "DO(IO1)_2") (pintype "bidirectional"))
      (node (ref "U2") (pin "27") (pinfunction "IO2_27") (pintype "bidirectional"))
    )
    (net (code "20") (name "MOSI") (class "Default")
      (node (ref "D8") (pin "2") (pinfunction "2_2") (pintype "passive"))
      (node (ref "J1") (pin "14") (pinfunction "14_14") (pintype "bidirectional"))
      (node (ref "J4") (pin "P3") (pinfunction "CMD_P3") (pintype "bidirectional"))
      (node (ref "R6") (pin "1") (pinfunction "1_1") (pintype "passive"))
      (node (ref "TPMOSI") (pin "TP") (pinfunction "TP_TP") (pintype "input"))
      (node (ref "U1") (pin "5") (pinfunction "DI(IO0)_5") (pintype "bidirectional"))
      (node (ref "U2") (pin "7") (pinfunction "IO7_7") (pintype "bidirectional"))
    )
    (net (code "21") (name "Net-(CHG_LED-PadC)") (class "Default")
      (node (ref "CHG_LED") (pin "C") (pinfunction "C_C") (pintype "passive"))
      (node (ref "R1_BAT") (pin "1") (pinfunction "1_1") (pintype "passive"))
    )
    (net (code "22") (name "Net-(D2-CATHODE)") (class "Default")
      (node (ref "C1_BAT1") (pin "1") (pinfunction "1_1") (pintype "passive"))
      (node (ref "D2") (pin "1") (pinfunction "CATHODE_1") (pintype "bidirectional"))
      (node (ref "IC4") (pin "1") (pinfunction "VIN_1") (pintype "bidirectional"))
      (node (ref "IC4") (pin "3") (pinfunction "CE_3") (pintype "bidirectional"))
      (node (ref "Q1") (pin "2") (pinfunction "S_2") (pintype "bidirectional"))
    )
    (net (code "23") (name "Net-(D3-A)") (class "Default")
      (node (ref "C4") (pin "1") (pinfunction "1_1") (pintype "passive"))
      (node (ref "D3") (pin "2") (pinfunction "A_2") (pintype "bidirectional"))
      (node (ref "D4") (pin "1") (pinfunction "K_1") (pintype "bidirectional"))
    )
    (net (code "24") (name "Net-(D7-CATHODE)") (class "Default")
      (node (ref "D7") (pin "1") (pinfunction "CATHODE_1") (pintype "bidirectional"))
      (node (ref "R_CAPACITOR") (pin "1") (pinfunction "1_1") (pintype "passive"))
    )
    (net (code "25") (name "Net-(EPD_C1-Pad2)") (class "Default")
      (node (ref "EPD_C1") (pin "2") (pinfunction "2_2") (pintype "passive"))
      (node (ref "J1") (pin "4") (pinfunction "4_4") (pintype "bidirectional"))
    )
    (net (code "26") (name "Net-(EPD_C2-Pad2)") (class "Default")
      (node (ref "EPD_C2") (pin "2") (pinfunction "2_2") (pintype "passive"))
      (node (ref "J1") (pin "5") (pinfunction "5_5") (pintype "bidirectional"))
    )
    (net (code "27") (name "Net-(EPD_C6-Pad2)") (class "Default")
      (node (ref "EPD_C6") (pin "2") (pinfunction "2_2") (pintype "passive"))
      (node (ref "J1") (pin "18") (pinfunction "18_18") (pintype "bidirectional"))
    )
    (net (code "28") (name "Net-(EPD_C7-Pad2)") (class "Default")
      (node (ref "EPD_C7") (pin "2") (pinfunction "2_2") (pintype "passive"))
      (node (ref "J1") (pin "19") (pinfunction "19_19") (pintype "bidirectional"))
    )
    (net (code "29") (name "Net-(EPD_C8-Pad2)") (class "Default")
      (node (ref "EPD_C8") (pin "2") (pinfunction "2_2") (pintype "passive"))
      (node (ref "J1") (pin "20") (pinfunction "20_20") (pintype "bidirectional"))
    )
    (net (code "30") (name "Net-(EPD_C10-Pad2)") (class "Default")
      (node (ref "EPD_C10") (pin "2") (pinfunction "2_2") (pintype "passive"))
      (node (ref "J1") (pin "22") (pinfunction "22_22") (pintype "bidirectional"))
    )
    (net (code "31") (name "Net-(EPD_C12-Pad2)") (class "Default")
      (node (ref "EPD_C12") (pin "2") (pinfunction "2_2") (pintype "passive"))
      (node (ref "J1") (pin "24") (pinfunction "24_24") (pintype "bidirectional"))
    )
    (net (code "32") (name "Net-(IC1-CT)") (class "Default")
      (node (ref "C_DELAY") (pin "1") (pinfunction "1_1") (pintype "passive"))
      (node (ref "IC1") (pin "5") (pinfunction "CT_5") (pintype "bidirectional"))
    )
    (net (code "33") (name "Net-(J2-PadA5)") (class "Default")
      (node (ref "J2") (pin "A5") (pinfunction "A5_A5") (pintype "bidirectional"))
      (node (ref "R2-USB1") (pin "2") (pinfunction "2_2") (pintype "passive"))
    )
    (net (code "34") (name "Net-(J2-PadB5)") (class "Default")
      (node (ref "J2") (pin "B5") (pinfunction "B5_B5") (pintype "bidirectional"))
      (node (ref "R2-USB") (pin "1") (pinfunction "1_1") (pintype "passive"))
    )
    (net (code "35") (name "Net-(MCP73831-PROG)") (class "Default")
      (node (ref "MCP73831") (pin "5") (pinfunction "PROG_5") (pintype "input"))
      (node (ref "R2_BAT") (pin "2") (pinfunction "2_2") (pintype "passive"))
    )
    (net (code "36") (name "Net-(MCP73831-STAT)") (class "Default")
      (node (ref "MCP73831") (pin "1") (pinfunction "STAT_1") (pintype "output"))
      (node (ref "R1_BAT") (pin "2") (pinfunction "2_2") (pintype "passive"))
    )
    (net (code "37") (name "PREVGH") (class "Default")
      (node (ref "D5") (pin "1") (pinfunction "K_1") (pintype "bidirectional"))
      (node (ref "EPD_C9") (pin "2") (pinfunction "2_2") (pintype "passive"))
      (node (ref "J1") (pin "21") (pinfunction "21_21") (pintype "bidirectional"))
    )
    (net (code "38") (name "PREVGL") (class "Default")
      (node (ref "D4") (pin "2") (pinfunction "A_2") (pintype "bidirectional"))
      (node (ref "EPD_C11") (pin "2") (pinfunction "2_2") (pintype "passive"))
      (node (ref "J1") (pin "23") (pinfunction "23_23") (pintype "bidirectional"))
    )
    (net (code "39") (name "RESE") (class "Default")
      (node (ref "J1") (pin "3") (pinfunction "3_3") (pintype "bidirectional"))
      (node (ref "Q3") (pin "2") (pinfunction "S_2") (pintype "bidirectional"))
      (node (ref "R3") (pin "2") (pinfunction "2_2") (pintype "passive"))
    )
    (net (code "40") (name "RESE'") (class "Default")
      (node (ref "R2") (pin "2") (pinfunction "2_2") (pintype "passive"))
      (node (ref "R3") (pin "1") (pinfunction "1_1") (pintype "passive"))
      (node (ref "SJ1") (pin "2") (pinfunction "2_2") (pintype "passive"))
    )
    (net (code "41") (name "RESET") (class "Default")
      (node (ref "C5") (pin "1") (pinfunction "1_1") (pintype "passive"))
      (node (ref "IC1") (pin "1") (pinfunction "VOUT_1") (pintype "bidirectional"))
      (node (ref "RESET_BUTTON") (pin "3") (pinfunction "3_3") (pintype "passive"))
      (node (ref "RESET_BUTTON") (pin "4") (pinfunction "4_4") (pintype "passive"))
      (node (ref "R_RESET") (pin "1") (pinfunction "1_1") (pintype "passive"))
      (node (ref "U2") (pin "3") (pinfunction "EN_3") (pintype "input"))
    )
    (net (code "42") (name "RTC_RST") (class "Default")
      (node (ref "U2") (pin "16") (pinfunction "IO18_16") (pintype "bidirectional"))
      (node (ref "U3") (pin "4") (pinfunction "~{RST}_4") (pintype "input"))
    )
    (net (code "43") (name "RX") (class "Default")
      (node (ref "TPRX") (pin "TP") (pinfunction "TP_TP") (pintype "input"))
      (node (ref "U2") (pin "24") (pinfunction "RXD0/GPIO17_24") (pintype "bidirectional"))
    )
    (net (code "44") (name "SCK") (class "Default")
      (node (ref "D9") (pin "2") (pinfunction "2_2") (pintype "passive"))
      (node (ref "J1") (pin "13") (pinfunction "13_13") (pintype "bidirectional"))
      (node (ref "J4") (pin "P5") (pinfunction "CLK_P5") (pintype "bidirectional"))
      (node (ref "R7") (pin "1") (pinfunction "1_1") (pintype "passive"))
      (node (ref "TPSCK") (pin "TP") (pinfunction "TP_TP") (pintype "input"))
      (node (ref "U1") (pin "6") (pinfunction "CLK_6") (pintype "input"))
      (node (ref "U2") (pin "6") (pinfunction "IO6_6") (pintype "bidirectional"))
    )
    (net (code "45") (name "SCL") (class "Default")
      (node (ref "J3") (pin "4") (pinfunction "4_4") (pintype "passive"))
      (node (ref "R2_PINH") (pin "1") (pinfunction "1_1") (pintype "passive"))
      (node (ref "SENSOR2") (pin "4") (pinfunction "SCK_4") (pintype "input"))
      (node (ref "U2") (pin "20") (pinfunction "IO22_20") (pintype "bidirectional"))
      (node (ref "U3") (pin "16") (pinfunction "SCL_16") (pintype "input"))
      (node (ref "U4") (pin "7") (pinfunction "SCL_7") (pintype "input"))
    )
    (net (code "46") (name "SDA") (class "Default")
      (node (ref "J3") (pin "3") (pinfunction "3_3") (pintype "passive"))
      (node (ref "R1_PINH") (pin "1") (pinfunction "1_1") (pintype "passive"))
      (node (ref "SENSOR2") (pin "3") (pinfunction "SDI_3") (pintype "bidirectional"))
      (node (ref "U2") (pin "19") (pinfunction "IO21_19") (pintype "bidirectional"))
      (node (ref "U3") (pin "15") (pinfunction "SDA_15") (pintype "bidirectional"))
      (node (ref "U4") (pin "8") (pinfunction "SDA_8") (pintype "bidirectional"))
    )
    (net (code "47") (name "SRC") (class "Default")
      (node (ref "C4") (pin "2") (pinfunction "2_2") (pintype "passive"))
      (node (ref "D5") (pin "2") (pinfunction "A_2") (pintype "bidirectional"))
      (node (ref "L1") (pin "2") (pinfunction "2_2") (pintype "passive"))
      (node (ref "Q3") (pin "3") (pinfunction "D_3") (pintype "bidirectional"))
    )
    (net (code "48") (name "SS_SD") (class "Default")
      (node (ref "D12") (pin "2") (pinfunction "2_2") (pintype "passive"))
      (node (ref "J4") (pin "P2") (pinfunction "CD/DAT3_P2") (pintype "bidirectional"))
      (node (ref "R10") (pin "1") (pinfunction "1_1") (pintype "passive"))
      (node (ref "U2") (pin "4") (pinfunction "IO4_4") (pintype "bidirectional"))
    )
    (net (code "49") (name "TX") (class "Default")
      (node (ref "TPTX") (pin "TP") (pinfunction "TP_TP") (pintype "input"))
      (node (ref "U2") (pin "25") (pinfunction "TXD0/GPIO16_25") (pintype "bidirectional"))
    )
    (net (code "50") (name "USB_D+") (class "Default")
      (node (ref "D1") (pin "1") (pinfunction "I/O1_1_1") (pintype "bidirectional"))
      (node (ref "U2") (pin "14") (pinfunction "IO13_14") (pintype "bidirectional"))
    )
    (net (code "51") (name "USB_D-") (class "Default")
      (node (ref "D1") (pin "3") (pinfunction "I/O2_1_3") (pintype "bidirectional"))
      (node (ref "U2") (pin "13") (pinfunction "IO12_13") (pintype "bidirectional"))
    )
    (net (code "52") (name "VBAT") (class "Default")
      (node (ref "C2_BAT") (pin "1") (pinfunction "1_1") (pintype "passive"))
      (node (ref "MCP73831") (pin "3") (pinfunction "VBAT_3") (pintype "power_in"))
      (node (ref "Q1") (pin "3") (pinfunction "D_3") (pintype "bidirectional"))
      (node (ref "TPVBAT") (pin "TP") (pinfunction "TP_TP") (pintype "input"))
      (node (ref "U4") (pin "2") (pinfunction "CELL_2") (pintype "power_in"))
      (node (ref "U4") (pin "3") (pinfunction "VDD_3") (pintype "power_in"))
    )
    (net (code "53") (name "VBUS") (class "Default")
      (node (ref "C1_BAT") (pin "1") (pinfunction "1_1") (pintype "passive"))
      (node (ref "C4_USB") (pin "1") (pinfunction "1_1") (pintype "passive"))
      (node (ref "C5_USB") (pin "1") (pinfunction "1_1") (pintype "passive"))
      (node (ref "CHG_LED") (pin "A") (pinfunction "A_A") (pintype "passive"))
      (node (ref "D1") (pin "5") (pinfunction "VBUS_5") (pintype "bidirectional"))
      (node (ref "D2") (pin "2") (pinfunction "ANODE_2") (pintype "bidirectional"))
      (node (ref "MCP73831") (pin "4") (pinfunction "VIN_4") (pintype "power_in"))
      (node (ref "PFMF.050.1") (pin "2") (pinfunction "2_2") (pintype "passive"))
      (node (ref "Q1") (pin "1") (pinfunction "G_1") (pintype "bidirectional"))
      (node (ref "R1_PWRUSB") (pin "2") (pinfunction "2_2") (pintype "passive"))
      (node (ref "TPVBUS") (pin "TP") (pinfunction "TP_TP") (pintype "input"))
    )
    (net (code "54") (name "VRTC") (class "Default")
      (node (ref "C11") (pin "1") (pinfunction "1_1") (pintype "passive"))
      (node (ref "C8") (pin "1") (pinfunction "1_1") (pintype "passive"))
      (node (ref "R_CAPACITOR") (pin "2") (pinfunction "2_2") (pintype "passive"))
      (node (ref "U3") (pin "14") (pinfunction "VBAT_14") (pintype "power_in"))
    )
    (net (code "55") (name "VUSB") (class "Default")
      (node (ref "J2") (pin "A4") (pinfunction "A4_A4") (pintype "bidirectional"))
      (node (ref "J2") (pin "A9") (pinfunction "A9_A9") (pintype "bidirectional"))
      (node (ref "J2") (pin "B4") (pinfunction "B4_B4") (pintype "bidirectional"))
      (node (ref "J2") (pin "B9") (pinfunction "B9_B9") (pintype "bidirectional"))
      (node (ref "PFMF.050.1") (pin "1") (pinfunction "1_1") (pintype "passive"))
    )
    (net (code "56") (name "unconnected-(IC1-NC-Pad4)") (class "Default")
      (node (ref "IC1") (pin "4") (pinfunction "NC_4") (pintype "no_connect"))
    )
    (net (code "57") (name "unconnected-(IC4-NC-Pad4)") (class "Default")
      (node (ref "IC4") (pin "4") (pinfunction "NC_4") (pintype "no_connect"))
    )
    (net (code "58") (name "unconnected-(J1-Pad1)") (class "Default")
      (node (ref "J1") (pin "1") (pinfunction "1_1") (pintype "bidirectional"))
    )
    (net (code "59") (name "unconnected-(J1-Pad6)") (class "Default")
      (node (ref "J1") (pin "6") (pinfunction "6_6") (pintype "bidirectional"))
    )
    (net (code "60") (name "unconnected-(J1-Pad7)") (class "Default")
      (node (ref "J1") (pin "7") (pinfunction "7_7") (pintype "bidirectional"))
    )
    (net (code "61") (name "unconnected-(J2-PadA8)") (class "Default")
      (node (ref "J2") (pin "A8") (pinfunction "A8_A8") (pintype "bidirectional"))
    )
    (net (code "62") (name "unconnected-(J2-PadB8)") (class "Default")
      (node (ref "J2") (pin "B8") (pinfunction "B8_B8") (pintype "bidirectional"))
    )
    (net (code "63") (name "unconnected-(J4-DAT1-PadP8)") (class "Default")
      (node (ref "J4") (pin "P8") (pinfunction "DAT1_P8") (pintype "bidirectional"))
    )
    (net (code "64") (name "unconnected-(J4-DAT2-PadP1)") (class "Default")
      (node (ref "J4") (pin "P1") (pinfunction "DAT2_P1") (pintype "bidirectional"))
    )
    (net (code "65") (name "unconnected-(J4-DETECTION_1-PadS1)") (class "Default")
      (node (ref "J4") (pin "S1") (pinfunction "DETECTION_1_S1") (pintype "bidirectional"))
    )
    (net (code "66") (name "unconnected-(J4-DETECTION_2-PadS2)") (class "Default")
      (node (ref "J4") (pin "S2") (pinfunction "DETECTION_2_S2") (pintype "bidirectional"))
    )
    (net (code "67") (name "unconnected-(U2-NC-Pad22)") (class "Default")
      (node (ref "U2") (pin "22") (pinfunction "NC_22") (pintype "no_connect"))
    )
    (net (code "68") (name "unconnected-(U4-~{ALERT}-Pad5)") (class "Default")
      (node (ref "U4") (pin "5") (pinfunction "~{ALERT}_5") (pintype "output"))
    )
  )
)
